# dac_DAC1220.net
KiCad netlist of a schematic drawn in Altium Designer
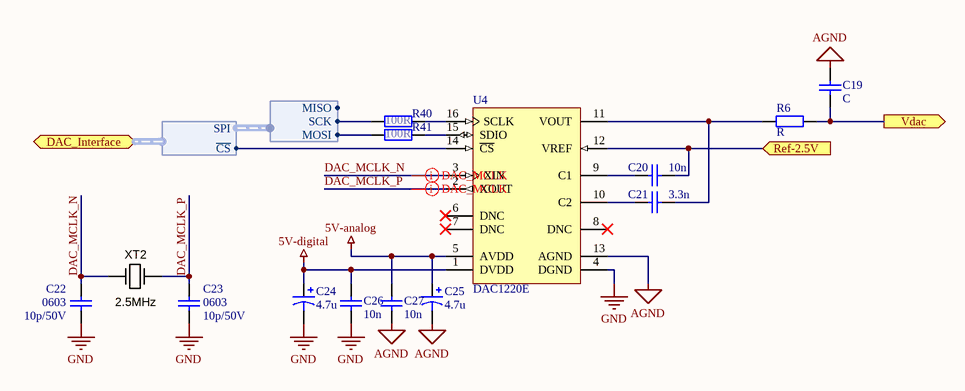
[diagram p0: dac_DAC1220.SchDoc]

(export (version "E")
  (design (tool "Eeschema 10.0.6"))
  (components
    (comp (ref "C19")
      (value "C")
      (footprint "C0603")
      (description "Generic capacitor")
      (libsource (lib "GG") (part "Cap"))
    )
    (comp (ref "C20")
      (value "10n")
      (footprint "C0603")
      (description "Generic capacitor")
      (libsource (lib "GG") (part "Cap"))
    )
    (comp (ref "C21")
      (value "3.3n")
      (footprint "C0603")
      (description "Generic capacitor")
      (libsource (lib "GG") (part "Cap"))
    )
    (comp (ref "C22")
      (value "10p/50V")
      (footprint "SMD_Capacitor_0603")
      (description "Ceramic Cap Murata Automotive 10p/50V C0G 0603")
      (fields
        (field (name "MANUFACTURER") "Murata")
        (field (name "MANUFACTURERPARTNUMBER") "GCM1885C1H100JA16D")
        (field (name "PACKAGE") "0603")
      )
      (libsource (lib "capacitors") (part "Cer_GCM1885C1H100JA16D"))
    )
    (comp (ref "C23")
      (value "10p/50V")
      (footprint "SMD_Capacitor_0603")
      (description "Ceramic Cap Murata Automotive 10p/50V C0G 0603")
      (fields
        (field (name "MANUFACTURER") "Murata")
        (field (name "MANUFACTURERPARTNUMBER") "GCM1885C1H100JA16D")
        (field (name "PACKAGE") "0603")
      )
      (libsource (lib "capacitors") (part "Cer_GCM1885C1H100JA16D"))
    )
    (comp (ref "C24")
      (value "4.7u")
      (footprint "Tantalum_cap_B")
      (description "Polarized Capacitor")
      (libsource (lib "GG") (part "Cap Pol"))
    )
    (comp (ref "C25")
      (value "4.7u")
      (footprint "Tantalum_cap_B")
      (description "Polarized Capacitor")
      (libsource (lib "GG") (part "Cap Pol"))
    )
    (comp (ref "C26")
      (value "10n")
      (footprint "C0603")
      (description "Generic capacitor")
      (libsource (lib "GG") (part "Cap"))
    )
    (comp (ref "C27")
      (value "10n")
      (footprint "C0603")
      (description "Generic capacitor")
      (libsource (lib "GG") (part "Cap"))
    )
    (comp (ref "R6")
      (value "R")
      (footprint "0603")
      (description "Generic resistor")
      (libsource (lib "GG") (part "Res"))
    )
    (comp (ref "R40")
      (value "100R")
      (footprint "0603")
      (description "Generic resistor")
      (libsource (lib "GG") (part "Res"))
    )
    (comp (ref "R41")
      (value "100R")
      (footprint "0603")
      (description "Generic resistor")
      (libsource (lib "GG") (part "Res"))
    )
    (comp (ref "U4")
      (value "DAC1220E")
      (footprint "TI-DBQ16_N")
      (description "20-Bit Delta-Sigma Low Power DAC, -40 to 85 degC, 16-pin SOP (DBQ16), Green (RoHS & no Sb/Br)")
      (fields (field (name "MANUFACTURER") "Texas Instruments"))
      (libsource (lib "TI Data Converters Digital to Analog Converter") (part "DAC1220E"))
    )
    (comp (ref "XT2")
      (value "2.5MHz")
      (footprint "HC49U")
      (description "AKER  C-2.4576-18-3050-X")
      (fields (field (name "TOLERANCE") "±50ppm"))
      (libsource (lib "crystal") (part "Crystal"))
    )
  )
  (nets
    (net (code "4") (name "/DAC_MCLK_N") (class "Default")
      (node (ref "C22") (pin "1") (pinfunction "1_1") (pintype "passive"))
      (node (ref "U4") (pin "3") (pinfunction "XIN_3") (pintype "input"))
      (node (ref "XT2") (pin "1") (pinfunction "IN_1") (pintype "passive"))
    )
    (net (code "5") (name "/DAC_MCLK_P") (class "Default")
      (node (ref "C23") (pin "1") (pinfunction "1_1") (pintype "passive"))
      (node (ref "U4") (pin "2") (pinfunction "XOUT_2") (pintype "output"))
      (node (ref "XT2") (pin "2") (pinfunction "OUT_2") (pintype "passive"))
    )
    (net (code "6") (name "/MOSI") (class "Default")
      (node (ref "R41") (pin "1") (pinfunction "1_1") (pintype "passive"))
    )
    (net (code "7") (name "/Ref-2.5V") (class "Default")
      (node (ref "C20") (pin "2") (pinfunction "2_2") (pintype "passive"))
      (node (ref "U4") (pin "12") (pinfunction "VREF_12") (pintype "input"))
    )
    (net (code "8") (name "/SCK") (class "Default")
      (node (ref "R40") (pin "1") (pinfunction "1_1") (pintype "passive"))
    )
    (net (code "9") (name "/Vdac") (class "Default")
      (node (ref "C19") (pin "1") (pinfunction "1_1") (pintype "passive"))
      (node (ref "R6") (pin "2") (pinfunction "2_2") (pintype "passive"))
    )
    (net (code "11") (name "/~{CS}") (class "Default")
      (node (ref "U4") (pin "14") (pinfunction "~{CS}_14") (pintype "input"))
    )
    (net (code "12") (name "5V-analog") (class "Default")
      (node (ref "C25") (pin "1") (pinfunction "1_1") (pintype "passive"))
      (node (ref "C27") (pin "1") (pinfunction "1_1") (pintype "passive"))
      (node (ref "U4") (pin "5") (pinfunction "AVDD_5") (pintype "power_in"))
    )
    (net (code "13") (name "5V-digital") (class "Default")
      (node (ref "C24") (pin "1") (pinfunction "1_1") (pintype "passive"))
      (node (ref "C26") (pin "1") (pinfunction "1_1") (pintype "passive"))
      (node (ref "U4") (pin "1") (pinfunction "DVDD_1") (pintype "power_in"))
    )
    (net (code "14") (name "AGND") (class "Default")
      (node (ref "C19") (pin "2") (pinfunction "2_2") (pintype "passive"))
      (node (ref "C25") (pin "2") (pinfunction "2_2") (pintype "passive"))
      (node (ref "C27") (pin "2") (pinfunction "2_2") (pintype "passive"))
      (node (ref "U4") (pin "13") (pinfunction "AGND_13") (pintype "power_in"))
    )
    (net (code "15") (name "GND") (class "Default")
      (node (ref "C22") (pin "2") (pinfunction "2_2") (pintype "passive"))
      (node (ref "C23") (pin "2") (pinfunction "2_2") (pintype "passive"))
      (node (ref "C24") (pin "2") (pinfunction "2_2") (pintype "passive"))
      (node (ref "C26") (pin "2") (pinfunction "2_2") (pintype "passive"))
      (node (ref "U4") (pin "4") (pinfunction "DGND_4") (pintype "power_in"))
    )
    (net (code "16") (name "Net-(U4-C1)") (class "Default")
      (node (ref "C20") (pin "1") (pinfunction "1_1") (pintype "passive"))
      (node (ref "U4") (pin "9") (pinfunction "C1_9") (pintype "passive"))
    )
    (net (code "17") (name "Net-(U4-C2)") (class "Default")
      (node (ref "C21") (pin "1") (pinfunction "1_1") (pintype "passive"))
      (node (ref "U4") (pin "10") (pinfunction "C2_10") (pintype "passive"))
    )
    (net (code "18") (name "Net-(U4-SCLK)") (class "Default")
      (node (ref "R40") (pin "2") (pinfunction "2_2") (pintype "passive"))
      (node (ref "U4") (pin "16") (pinfunction "SCLK_16") (pintype "input"))
    )
    (net (code "19") (name "Net-(U4-SDIO)") (class "Default")
      (node (ref "R41") (pin "2") (pinfunction "2_2") (pintype "passive"))
      (node (ref "U4") (pin "15") (pinfunction "SDIO_15") (pintype "bidirectional"))
    )
    (net (code "20") (name "Net-(U4-VOUT)") (class "Default")
      (node (ref "C21") (pin "2") (pinfunction "2_2") (pintype "passive"))
      (node (ref "R6") (pin "1") (pinfunction "1_1") (pintype "passive"))
      (node (ref "U4") (pin "11") (pinfunction "VOUT_11") (pintype "tri_state"))
    )
    (net (code "21") (name "unconnected-(U4-DNC-Pad6)") (class "Default")
      (node (ref "U4") (pin "6") (pinfunction "DNC_6") (pintype "passive+no_connect"))
    )
    (net (code "22") (name "unconnected-(U4-DNC-Pad7)") (class "Default")
      (node (ref "U4") (pin "7") (pinfunction "DNC_7") (pintype "passive+no_connect"))
    )
    (net (code "23") (name "unconnected-(U4-DNC-Pad8)") (class "Default")
      (node (ref "U4") (pin "8") (pinfunction "DNC_8") (pintype "passive+no_connect"))
    )
  )
)
